# DHT11_v2_SCH.net
KiCad netlist of a schematic drawn in Altium Designer
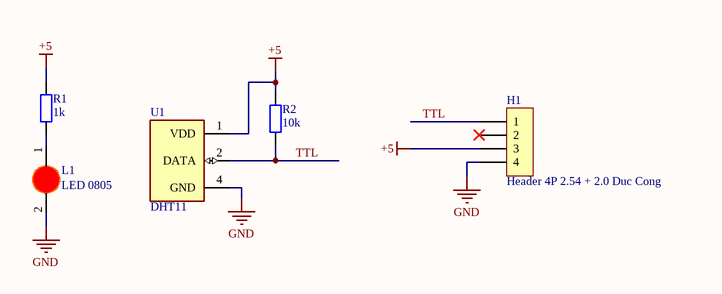
[diagram p0: DHT11_v2_SCH.SchDoc]

(export (version "E")
  (design (tool "Eeschema 10.0.6"))
  (components
    (comp (ref "H1")
      (value "Header 4P 2.54 + 2.0 Duc Cong")
      (footprint "Header 4P DC 2.54 + 2.0")
      (description "Cắm")
      (libsource (lib "namnt_Lib") (part "Header 4P 2.54 + 2.0 Duc Cong"))
    )
    (comp (ref "L1")
      (value "LED 0805")
      (footprint "LED-0805-Red")
      (description "Dán")
      (libsource (lib "namnt_Lib") (part "LED 0805 Do"))
    )
    (comp (ref "R1")
      (value "1k")
      (footprint "tro smd 0603")
      (description "Dán")
      (libsource (lib "namnt_Lib") (part "Tro 0603 1% 10k"))
    )
    (comp (ref "R2")
      (value "10k")
      (footprint "tro smd 0603")
      (description "Dán")
      (libsource (lib "namnt_Lib") (part "Tro 0603 1% 10k"))
    )
    (comp (ref "U1")
      (value "DHT11")
      (footprint "DHT11")
      (description "DHT11 basic temperature-humidity sensor + extras")
      (fields (field (name "MF") "Adafruit Industries") (field (name "MP") "ADA386"))
      (libsource (lib "namnt_Lib") (part "DHT11"))
    )
  )
  (nets
    (net (code "1") (name "+5") (class "Default")
      (node (ref "H1") (pin "3") (pinfunction "3_3") (pintype "passive"))
      (node (ref "R1") (pin "2") (pinfunction "2_2") (pintype "passive"))
      (node (ref "R2") (pin "2") (pinfunction "2_2") (pintype "passive"))
      (node (ref "U1") (pin "1") (pinfunction "VDD_1") (pintype "power_in"))
    )
    (net (code "2") (name "/TTL") (class "Default")
      (node (ref "H1") (pin "1") (pinfunction "1_1") (pintype "passive"))
      (node (ref "R2") (pin "1") (pinfunction "1_1") (pintype "passive"))
      (node (ref "U1") (pin "2") (pinfunction "DATA_2") (pintype "bidirectional"))
    )
    (net (code "3") (name "GND") (class "Default")
      (node (ref "H1") (pin "4") (pinfunction "4_4") (pintype "passive"))
      (node (ref "L1") (pin "2") (pinfunction "K_2") (pintype "passive"))
      (node (ref "U1") (pin "4") (pinfunction "GND_4") (pintype "power_in"))
    )
    (net (code "4") (name "Net-(L1-A)") (class "Default")
      (node (ref "L1") (pin "1") (pinfunction "A_1") (pintype "passive"))
      (node (ref "R1") (pin "1") (pinfunction "1_1") (pintype "passive"))
    )
    (net (code "5") (name "unconnected-(H1-Pad2)") (class "Default")
      (node (ref "H1") (pin "2") (pinfunction "2_2") (pintype "passive+no_connect"))
    )
  )
)
